# PWR_CORE.net
KiCad netlist of a schematic drawn in Altium Designer
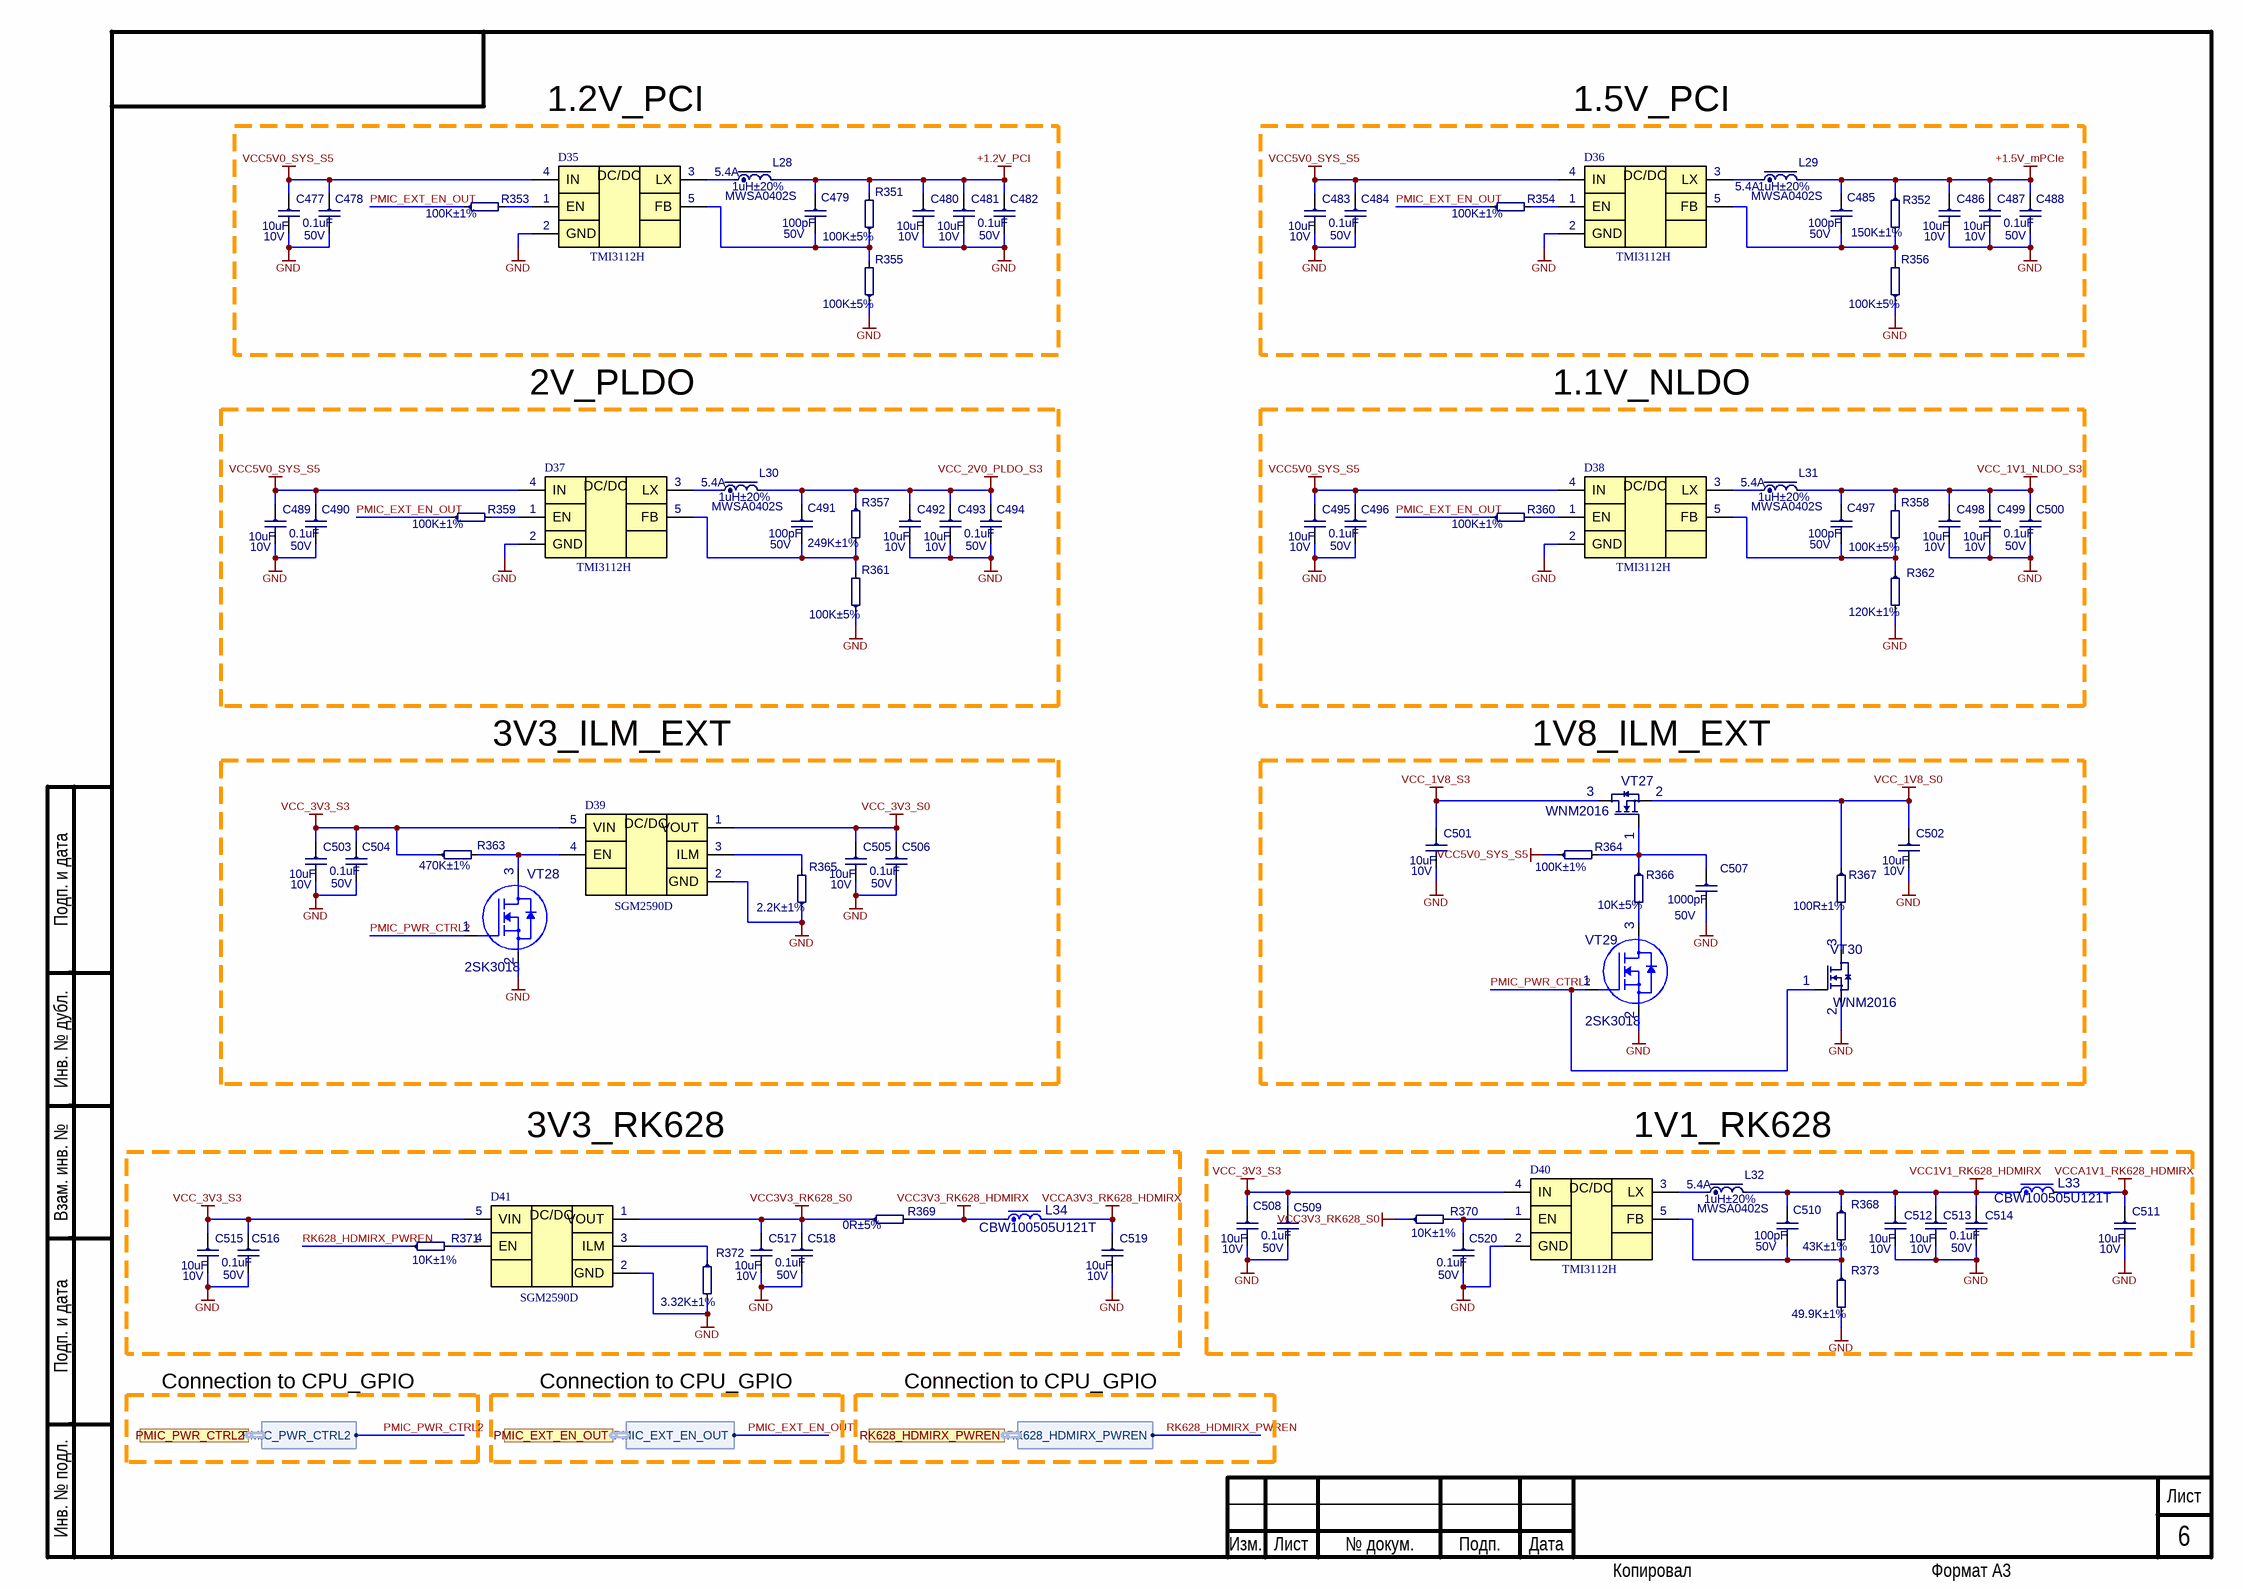
[diagram p0: PWR_CORE.SchDoc]

(export (version "E")
  (design (tool "Eeschema 10.0.6"))
  (components
    (comp (ref "C477")
      (value "10uF")
      (footprint "C0603")
      (fields
        (field (name "VOLTAGE") "10V")
        (field (name "PART NUMBER") "0603-X5R-10V-10uF±10%")
        (field (name "TOLERANCE") "10%")
        (field (name "MANUFACTURER") "Yageo")
      )
      (libsource (lib "ATB") (part "C"))
    )
    (comp (ref "C478")
      (value "0.1uF")
      (footprint "C0402")
      (fields
        (field (name "VOLTAGE") "50V")
        (field (name "PART NUMBER") "0402-X5R-50V-0.1uF±10%")
        (field (name "TOLERANCE") "10%")
        (field (name "MANUFACTURER") "Yageo")
      )
      (libsource (lib "ATB") (part "C"))
    )
    (comp (ref "C479")
      (value "100pF")
      (footprint "C0402")
      (fields
        (field (name "VOLTAGE") "50V")
        (field (name "PART NUMBER") "0402-NP0-50V-100pF±5%")
        (field (name "TOLERANCE") "5%")
        (field (name "MANUFACTURER") "Yageo")
      )
      (libsource (lib "ATB") (part "C"))
    )
    (comp (ref "C480")
      (value "10uF")
      (footprint "C0603")
      (fields
        (field (name "VOLTAGE") "10V")
        (field (name "PART NUMBER") "0603-X5R-10V-10uF±10%")
        (field (name "TOLERANCE") "10%")
        (field (name "MANUFACTURER") "Yageo")
      )
      (libsource (lib "ATB") (part "C"))
    )
    (comp (ref "C481")
      (value "10uF")
      (footprint "C0603")
      (fields
        (field (name "VOLTAGE") "10V")
        (field (name "PART NUMBER") "0603-X5R-10V-10uF±10%")
        (field (name "TOLERANCE") "10%")
        (field (name "MANUFACTURER") "Yageo")
      )
      (libsource (lib "ATB") (part "C"))
    )
    (comp (ref "C482")
      (value "0.1uF")
      (footprint "C0402")
      (fields
        (field (name "VOLTAGE") "50V")
        (field (name "PART NUMBER") "0402-X5R-50V-0.1uF±10%")
        (field (name "TOLERANCE") "10%")
        (field (name "MANUFACTURER") "Yageo")
      )
      (libsource (lib "ATB") (part "C"))
    )
    (comp (ref "C483")
      (value "10uF")
      (footprint "C0603")
      (fields
        (field (name "VOLTAGE") "10V")
        (field (name "PART NUMBER") "0603-X5R-10V-10uF±10%")
        (field (name "TOLERANCE") "10%")
        (field (name "MANUFACTURER") "Yageo")
      )
      (libsource (lib "ATB") (part "C"))
    )
    (comp (ref "C484")
      (value "0.1uF")
      (footprint "C0402")
      (fields
        (field (name "VOLTAGE") "50V")
        (field (name "PART NUMBER") "0402-X5R-50V-0.1uF±10%")
        (field (name "TOLERANCE") "10%")
        (field (name "MANUFACTURER") "Yageo")
      )
      (libsource (lib "ATB") (part "C"))
    )
    (comp (ref "C485")
      (value "100pF")
      (footprint "C0402")
      (fields
        (field (name "VOLTAGE") "50V")
        (field (name "PART NUMBER") "0402-NP0-50V-100pF±5%")
        (field (name "TOLERANCE") "5%")
        (field (name "MANUFACTURER") "Yageo")
      )
      (libsource (lib "ATB") (part "C"))
    )
    (comp (ref "C486")
      (value "10uF")
      (footprint "C0603")
      (fields
        (field (name "VOLTAGE") "10V")
        (field (name "PART NUMBER") "0603-X5R-10V-10uF±10%")
        (field (name "TOLERANCE") "10%")
        (field (name "MANUFACTURER") "Yageo")
      )
      (libsource (lib "ATB") (part "C"))
    )
    (comp (ref "C487")
      (value "10uF")
      (footprint "C0603")
      (fields
        (field (name "VOLTAGE") "10V")
        (field (name "PART NUMBER") "0603-X5R-10V-10uF±10%")
        (field (name "TOLERANCE") "10%")
        (field (name "MANUFACTURER") "Yageo")
      )
      (libsource (lib "ATB") (part "C"))
    )
    (comp (ref "C488")
      (value "0.1uF")
      (footprint "C0402")
      (fields
        (field (name "VOLTAGE") "50V")
        (field (name "PART NUMBER") "0402-X5R-50V-0.1uF±10%")
        (field (name "TOLERANCE") "10%")
        (field (name "MANUFACTURER") "Yageo")
      )
      (libsource (lib "ATB") (part "C"))
    )
    (comp (ref "C489")
      (value "10uF")
      (footprint "C0603")
      (fields
        (field (name "VOLTAGE") "10V")
        (field (name "PART NUMBER") "0603-X5R-10V-10uF±10%")
        (field (name "TOLERANCE") "10%")
        (field (name "MANUFACTURER") "Yageo")
      )
      (libsource (lib "ATB") (part "C"))
    )
    (comp (ref "C490")
      (value "0.1uF")
      (footprint "C0402")
      (fields
        (field (name "VOLTAGE") "50V")
        (field (name "PART NUMBER") "0402-X5R-50V-0.1uF±10%")
        (field (name "TOLERANCE") "10%")
        (field (name "MANUFACTURER") "Yageo")
      )
      (libsource (lib "ATB") (part "C"))
    )
    (comp (ref "C491")
      (value "100pF")
      (footprint "C0402")
      (fields
        (field (name "VOLTAGE") "50V")
        (field (name "PART NUMBER") "0402-NP0-50V-100pF±5%")
        (field (name "TOLERANCE") "5%")
        (field (name "MANUFACTURER") "Yageo")
      )
      (libsource (lib "ATB") (part "C"))
    )
    (comp (ref "C492")
      (value "10uF")
      (footprint "C0603")
      (fields
        (field (name "VOLTAGE") "10V")
        (field (name "PART NUMBER") "0603-X5R-10V-10uF±10%")
        (field (name "TOLERANCE") "10%")
        (field (name "MANUFACTURER") "Yageo")
      )
      (libsource (lib "ATB") (part "C"))
    )
    (comp (ref "C493")
      (value "10uF")
      (footprint "C0603")
      (fields
        (field (name "VOLTAGE") "10V")
        (field (name "PART NUMBER") "0603-X5R-10V-10uF±10%")
        (field (name "TOLERANCE") "10%")
        (field (name "MANUFACTURER") "Yageo")
      )
      (libsource (lib "ATB") (part "C"))
    )
    (comp (ref "C494")
      (value "0.1uF")
      (footprint "C0402")
      (fields
        (field (name "VOLTAGE") "50V")
        (field (name "PART NUMBER") "0402-X5R-50V-0.1uF±10%")
        (field (name "TOLERANCE") "10%")
        (field (name "MANUFACTURER") "Yageo")
      )
      (libsource (lib "ATB") (part "C"))
    )
    (comp (ref "C495")
      (value "10uF")
      (footprint "C0603")
      (fields
        (field (name "VOLTAGE") "10V")
        (field (name "PART NUMBER") "0603-X5R-10V-10uF±10%")
        (field (name "TOLERANCE") "10%")
        (field (name "MANUFACTURER") "Yageo")
      )
      (libsource (lib "ATB") (part "C"))
    )
    (comp (ref "C496")
      (value "0.1uF")
      (footprint "C0402")
      (fields
        (field (name "VOLTAGE") "50V")
        (field (name "PART NUMBER") "0402-X5R-50V-0.1uF±10%")
        (field (name "TOLERANCE") "10%")
        (field (name "MANUFACTURER") "Yageo")
      )
      (libsource (lib "ATB") (part "C"))
    )
    (comp (ref "C497")
      (value "100pF")
      (footprint "C0402")
      (fields
        (field (name "VOLTAGE") "50V")
        (field (name "PART NUMBER") "0402-NP0-50V-100pF±5%")
        (field (name "TOLERANCE") "5%")
        (field (name "MANUFACTURER") "Yageo")
      )
      (libsource (lib "ATB") (part "C"))
    )
    (comp (ref "C498")
      (value "10uF")
      (footprint "C0603")
      (fields
        (field (name "VOLTAGE") "10V")
        (field (name "PART NUMBER") "0603-X5R-10V-10uF±10%")
        (field (name "TOLERANCE") "10%")
        (field (name "MANUFACTURER") "Yageo")
      )
      (libsource (lib "ATB") (part "C"))
    )
    (comp (ref "C499")
      (value "10uF")
      (footprint "C0603")
      (fields
        (field (name "VOLTAGE") "10V")
        (field (name "PART NUMBER") "0603-X5R-10V-10uF±10%")
        (field (name "TOLERANCE") "10%")
        (field (name "MANUFACTURER") "Yageo")
      )
      (libsource (lib "ATB") (part "C"))
    )
    (comp (ref "C500")
      (value "0.1uF")
      (footprint "C0402")
      (fields
        (field (name "VOLTAGE") "50V")
        (field (name "PART NUMBER") "0402-X5R-50V-0.1uF±10%")
        (field (name "TOLERANCE") "10%")
        (field (name "MANUFACTURER") "Yageo")
      )
      (libsource (lib "ATB") (part "C"))
    )
    (comp (ref "C501")
      (value "10uF")
      (footprint "C0603")
      (fields
        (field (name "VOLTAGE") "10V")
        (field (name "PART NUMBER") "0603-X5R-10V-10uF±10%")
        (field (name "TOLERANCE") "10%")
        (field (name "MANUFACTURER") "Yageo")
      )
      (libsource (lib "ATB") (part "C"))
    )
    (comp (ref "C502")
      (value "10uF")
      (footprint "C0603")
      (fields
        (field (name "VOLTAGE") "10V")
        (field (name "PART NUMBER") "0603-X5R-10V-10uF±10%")
        (field (name "TOLERANCE") "10%")
        (field (name "MANUFACTURER") "Yageo")
      )
      (libsource (lib "ATB") (part "C"))
    )
    (comp (ref "C503")
      (value "10uF")
      (footprint "C0603")
      (fields
        (field (name "VOLTAGE") "10V")
        (field (name "PART NUMBER") "0603-X5R-10V-10uF±10%")
        (field (name "TOLERANCE") "10%")
        (field (name "MANUFACTURER") "Yageo")
      )
      (libsource (lib "ATB") (part "C"))
    )
    (comp (ref "C504")
      (value "0.1uF")
      (footprint "C0402")
      (fields
        (field (name "VOLTAGE") "50V")
        (field (name "PART NUMBER") "0402-X5R-50V-0.1uF±10%")
        (field (name "TOLERANCE") "10%")
        (field (name "MANUFACTURER") "Yageo")
      )
      (libsource (lib "ATB") (part "C"))
    )
    (comp (ref "C505")
      (value "10uF")
      (footprint "C0603")
      (fields
        (field (name "VOLTAGE") "10V")
        (field (name "PART NUMBER") "0603-X5R-10V-10uF±10%")
        (field (name "TOLERANCE") "10%")
        (field (name "MANUFACTURER") "Yageo")
      )
      (libsource (lib "ATB") (part "C"))
    )
    (comp (ref "C506")
      (value "0.1uF")
      (footprint "C0402")
      (fields
        (field (name "VOLTAGE") "50V")
        (field (name "PART NUMBER") "0402-X5R-50V-0.1uF±10%")
        (field (name "TOLERANCE") "10%")
        (field (name "MANUFACTURER") "Yageo")
      )
      (libsource (lib "ATB") (part "C"))
    )
    (comp (ref "C507")
      (value "1000pF")
      (footprint "C0402")
      (fields
        (field (name "VOLTAGE") "50V")
        (field (name "PART NUMBER") "0402-NP0-50V-1000pF±5%")
        (field (name "TOLERANCE") "5%")
        (field (name "MANUFACTURER") "Yageo")
      )
      (libsource (lib "ATB") (part "C"))
    )
    (comp (ref "C508")
      (value "10uF")
      (footprint "C0603")
      (fields
        (field (name "VOLTAGE") "10V")
        (field (name "PART NUMBER") "0603-X5R-10V-10uF±10%")
        (field (name "TOLERANCE") "10%")
        (field (name "MANUFACTURER") "Yageo")
      )
      (libsource (lib "ATB") (part "C"))
    )
    (comp (ref "C509")
      (value "0.1uF")
      (footprint "C0402")
      (fields
        (field (name "VOLTAGE") "50V")
        (field (name "PART NUMBER") "0402-X5R-50V-0.1uF±10%")
        (field (name "TOLERANCE") "10%")
        (field (name "MANUFACTURER") "Yageo")
      )
      (libsource (lib "ATB") (part "C"))
    )
    (comp (ref "C510")
      (value "100pF")
      (footprint "C0402")
      (fields
        (field (name "VOLTAGE") "50V")
        (field (name "PART NUMBER") "0402-NP0-50V-100pF±5%")
        (field (name "TOLERANCE") "5%")
        (field (name "MANUFACTURER") "Yageo")
      )
      (libsource (lib "ATB") (part "C"))
    )
    (comp (ref "C511")
      (value "10uF")
      (footprint "C0603")
      (fields
        (field (name "VOLTAGE") "10V")
        (field (name "PART NUMBER") "0603-X5R-10V-10uF±10%")
        (field (name "TOLERANCE") "10%")
        (field (name "MANUFACTURER") "Yageo")
      )
      (libsource (lib "ATB") (part "C"))
    )
    (comp (ref "C512")
      (value "10uF")
      (footprint "C0603")
      (fields
        (field (name "VOLTAGE") "10V")
        (field (name "PART NUMBER") "0603-X5R-10V-10uF±10%")
        (field (name "TOLERANCE") "10%")
        (field (name "MANUFACTURER") "Yageo")
      )
      (libsource (lib "ATB") (part "C"))
    )
    (comp (ref "C513")
      (value "10uF")
      (footprint "C0603")
      (fields
        (field (name "VOLTAGE") "10V")
        (field (name "PART NUMBER") "0603-X5R-10V-10uF±10%")
        (field (name "TOLERANCE") "10%")
        (field (name "MANUFACTURER") "Yageo")
      )
      (libsource (lib "ATB") (part "C"))
    )
    (comp (ref "C514")
      (value "0.1uF")
      (footprint "C0402")
      (fields
        (field (name "VOLTAGE") "50V")
        (field (name "PART NUMBER") "0402-X5R-50V-0.1uF±10%")
        (field (name "TOLERANCE") "10%")
        (field (name "MANUFACTURER") "Yageo")
      )
      (libsource (lib "ATB") (part "C"))
    )
    (comp (ref "C515")
      (value "10uF")
      (footprint "C0603")
      (fields
        (field (name "VOLTAGE") "10V")
        (field (name "PART NUMBER") "0603-X5R-10V-10uF±10%")
        (field (name "TOLERANCE") "10%")
        (field (name "MANUFACTURER") "Yageo")
      )
      (libsource (lib "ATB") (part "C"))
    )
    (comp (ref "C516")
      (value "0.1uF")
      (footprint "C0402")
      (fields
        (field (name "VOLTAGE") "50V")
        (field (name "PART NUMBER") "0402-X5R-50V-0.1uF±10%")
        (field (name "TOLERANCE") "10%")
        (field (name "MANUFACTURER") "Yageo")
      )
      (libsource (lib "ATB") (part "C"))
    )
    (comp (ref "C517")
      (value "10uF")
      (footprint "C0603")
      (fields
        (field (name "VOLTAGE") "10V")
        (field (name "PART NUMBER") "0603-X5R-10V-10uF±10%")
        (field (name "TOLERANCE") "10%")
        (field (name "MANUFACTURER") "Yageo")
      )
      (libsource (lib "ATB") (part "C"))
    )
    (comp (ref "C518")
      (value "0.1uF")
      (footprint "C0402")
      (fields
        (field (name "VOLTAGE") "50V")
        (field (name "PART NUMBER") "0402-X5R-50V-0.1uF±10%")
        (field (name "TOLERANCE") "10%")
        (field (name "MANUFACTURER") "Yageo")
      )
      (libsource (lib "ATB") (part "C"))
    )
    (comp (ref "C519")
      (value "10uF")
      (footprint "C0603")
      (fields
        (field (name "VOLTAGE") "10V")
        (field (name "PART NUMBER") "0603-X5R-10V-10uF±10%")
        (field (name "TOLERANCE") "10%")
        (field (name "MANUFACTURER") "Yageo")
      )
      (libsource (lib "ATB") (part "C"))
    )
    (comp (ref "C520")
      (value "0.1uF")
      (footprint "C0402")
      (fields
        (field (name "VOLTAGE") "50V")
        (field (name "PART NUMBER") "0402-X5R-50V-0.1uF±10%")
        (field (name "TOLERANCE") "10%")
        (field (name "MANUFACTURER") "Yageo")
      )
      (libsource (lib "ATB") (part "C"))
    )
    (comp (ref "D35")
      (value "TMI3112H")
      (footprint "TMI3112H")
      (description "Buck 2.3MHz Adjustable 2A 600mV~5.5V SOT-23-5 Voltage Regulators - DC DC Switching Regulators RoHS")
      (fields (field (name "MANUFACTURER") "TMI"))
      (libsource (lib "LIB_RK") (part "TMI3112H"))
    )
    (comp (ref "D36")
      (value "TMI3112H")
      (footprint "TMI3112H")
      (description "Buck 2.3MHz Adjustable 2A 600mV~5.5V SOT-23-5 Voltage Regulators - DC DC Switching Regulators RoHS")
      (fields (field (name "MANUFACTURER") "TMI"))
      (libsource (lib "LIB_RK") (part "TMI3112H"))
    )
    (comp (ref "D37")
      (value "TMI3112H")
      (footprint "TMI3112H")
      (description "Buck 2.3MHz Adjustable 2A 600mV~5.5V SOT-23-5 Voltage Regulators - DC DC Switching Regulators RoHS")
      (fields (field (name "MANUFACTURER") "TMI"))
      (libsource (lib "LIB_RK") (part "TMI3112H"))
    )
    (comp (ref "D38")
      (value "TMI3112H")
      (footprint "TMI3112H")
      (description "Buck 2.3MHz Adjustable 2A 600mV~5.5V SOT-23-5 Voltage Regulators - DC DC Switching Regulators RoHS")
      (fields (field (name "MANUFACTURER") "TMI"))
      (libsource (lib "LIB_RK") (part "TMI3112H"))
    )
    (comp (ref "D39")
      (value "SGM2590D")
      (footprint "SGM2590D")
      (fields (field (name "MANUFACTURER") "SGM"))
      (libsource (lib "LIB_RK") (part "SGM2590D"))
    )
    (comp (ref "D40")
      (value "TMI3112H")
      (footprint "TMI3112H")
      (description "Buck 2.3MHz Adjustable 2A 600mV~5.5V SOT-23-5 Voltage Regulators - DC DC Switching Regulators RoHS")
      (fields (field (name "MANUFACTURER") "TMI"))
      (libsource (lib "LIB_RK") (part "TMI3112H"))
    )
    (comp (ref "D41")
      (value "SGM2590D")
      (footprint "SGM2590D")
      (fields (field (name "MANUFACTURER") "SGM"))
      (libsource (lib "LIB_RK") (part "SGM2590D"))
    )
    (comp (ref "L28")
      (value "1uH±20%")
      (footprint "MWSA0402S")
      (description "5.4A 1uH ±20% 5.6A SMD 4.4x4.2mm Power Inductor")
      (fields
        (field (name "CURRENT") "5.4A")
        (field (name "CASE") "MWSA0402S")
        (field (name "PART NUMBER") "MWSA0402S-1R0MT")
        (field (name "TOLERANCE") "20%")
      )
      (libsource (lib "") (part "L_1"))
    )
    (comp (ref "L29")
      (value "1uH±20%")
      (footprint "MWSA0402S")
      (description "5.4A 1uH ±20% 5.6A SMD 4.4x4.2mm Power Inductor")
      (fields
        (field (name "CURRENT") "5.4A")
        (field (name "CASE") "MWSA0402S")
        (field (name "PART NUMBER") "MWSA0402S-1R0MT")
        (field (name "TOLERANCE") "20%")
      )
      (libsource (lib "") (part "L_1"))
    )
    (comp (ref "L30")
      (value "1uH±20%")
      (footprint "MWSA0402S")
      (description "5.4A 1uH ±20% 5.6A SMD 4.4x4.2mm Power Inductor")
      (fields
        (field (name "CURRENT") "5.4A")
        (field (name "CASE") "MWSA0402S")
        (field (name "PART NUMBER") "MWSA0402S-1R0MT")
        (field (name "TOLERANCE") "20%")
      )
      (libsource (lib "") (part "L_1"))
    )
    (comp (ref "L31")
      (value "1uH±20%")
      (footprint "MWSA0402S")
      (description "5.4A 1uH ±20% 5.6A SMD 4.4x4.2mm Power Inductor")
      (fields
        (field (name "CURRENT") "5.4A")
        (field (name "CASE") "MWSA0402S")
        (field (name "PART NUMBER") "MWSA0402S-1R0MT")
        (field (name "TOLERANCE") "20%")
      )
      (libsource (lib "") (part "L_1"))
    )
    (comp (ref "L32")
      (value "1uH±20%")
      (footprint "MWSA0402S")
      (description "5.4A 1uH ±20% 5.6A SMD 4.4x4.2mm Power Inductor")
      (fields
        (field (name "CURRENT") "5.4A")
        (field (name "CASE") "MWSA0402S")
        (field (name "PART NUMBER") "MWSA0402S-1R0MT")
        (field (name "TOLERANCE") "20%")
      )
      (libsource (lib "") (part "L_1"))
    )
    (comp (ref "L33")
      (value "CBW100505U121T")
      (footprint "L0402")
      (description "120Ω@100MHz  Ferrite Beads")
      (fields (field (name "TOLERANCE") "25%") (field (name "MANUFACTURER") "Murata Electronics"))
      (libsource (lib "ATB") (part "L"))
    )
    (comp (ref "L34")
      (value "CBW100505U121T")
      (footprint "L0402")
      (description "120Ω@100MHz  Ferrite Beads")
      (fields (field (name "TOLERANCE") "25%") (field (name "MANUFACTURER") "Murata Electronics"))
      (libsource (lib "ATB") (part "L"))
    )
    (comp (ref "R351")
      (value "100K±5%")
      (footprint "R0402")
      (fields
        (field (name "PART NUMBER") "0402-0.0625W-100K-100ppm±5%")
        (field (name "TOLERANCE") "5%")
        (field (name "MANUFACTURER") "Yageo")
      )
      (libsource (lib "ATB") (part "R"))
    )
    (comp (ref "R352")
      (value "150K±1%")
      (footprint "R0402")
      (fields
        (field (name "PART NUMBER") "0402-0.0625W-150K-100ppm±1%")
        (field (name "TOLERANCE") "1%")
        (field (name "MANUFACTURER") "Yageo")
      )
      (libsource (lib "ATB") (part "R"))
    )
    (comp (ref "R353")
      (value "100K±1%")
      (footprint "R0402")
      (description "Chip Resistor 0402 100kΩ ±1% 50V ±100ppm/℃ Thick Film")
      (fields (field (name "PART NUMBER") "0402-0.0625W-100K-100ppm±1%") (field (name "TOLERANCE") "1%"))
      (libsource (lib "ATB") (part "R"))
    )
    (comp (ref "R354")
      (value "100K±1%")
      (footprint "R0402")
      (description "Chip Resistor 0402 100kΩ ±1% 50V ±100ppm/℃ Thick Film")
      (fields (field (name "PART NUMBER") "0402-0.0625W-100K-100ppm±1%") (field (name "TOLERANCE") "1%"))
      (libsource (lib "ATB") (part "R"))
    )
    (comp (ref "R355")
      (value "100K±5%")
      (footprint "R0402")
      (fields
        (field (name "PART NUMBER") "0402-0.0625W-100K-100ppm±5%")
        (field (name "TOLERANCE") "5%")
        (field (name "MANUFACTURER") "Yageo")
      )
      (libsource (lib "ATB") (part "R"))
    )
    (comp (ref "R356")
      (value "100K±5%")
      (footprint "R0402")
      (fields
        (field (name "PART NUMBER") "0402-0.0625W-100K-100ppm±5%")
        (field (name "TOLERANCE") "5%")
        (field (name "MANUFACTURER") "Yageo")
      )
      (libsource (lib "ATB") (part "R"))
    )
    (comp (ref "R357")
      (value "249K±1%")
      (footprint "R0402")
      (fields
        (field (name "PART NUMBER") "0402-0.0625W-249K-100ppm±1%")
        (field (name "TOLERANCE") "1%")
        (field (name "MANUFACTURER") "Yageo")
      )
      (libsource (lib "ATB") (part "R"))
    )
    (comp (ref "R358")
      (value "100K±5%")
      (footprint "R0402")
      (fields
        (field (name "PART NUMBER") "0402-0.0625W-100K-100ppm±5%")
        (field (name "TOLERANCE") "5%")
        (field (name "MANUFACTURER") "Yageo")
      )
      (libsource (lib "ATB") (part "R"))
    )
    (comp (ref "R359")
      (value "100K±1%")
      (footprint "R0402")
      (description "Chip Resistor 0402 100kΩ ±1% 50V ±100ppm/℃ Thick Film")
      (fields (field (name "PART NUMBER") "0402-0.0625W-100K-100ppm±1%") (field (name "TOLERANCE") "1%"))
      (libsource (lib "ATB") (part "R"))
    )
    (comp (ref "R360")
      (value "100K±1%")
      (footprint "R0402")
      (description "Chip Resistor 0402 100kΩ ±1% 50V ±100ppm/℃ Thick Film")
      (fields (field (name "PART NUMBER") "0402-0.0625W-100K-100ppm±1%") (field (name "TOLERANCE") "1%"))
      (libsource (lib "ATB") (part "R"))
    )
    (comp (ref "R361")
      (value "100K±5%")
      (footprint "R0402")
      (fields
        (field (name "PART NUMBER") "0402-0.0625W-100K-100ppm±5%")
        (field (name "TOLERANCE") "5%")
        (field (name "MANUFACTURER") "Yageo")
      )
      (libsource (lib "ATB") (part "R"))
    )
    (comp (ref "R362")
      (value "120K±1%")
      (footprint "R0402")
      (fields
        (field (name "PART NUMBER") "0402-0.0625W-120K-100ppm±1%")
        (field (name "TOLERANCE") "1%")
        (field (name "MANUFACTURER") "Yageo")
      )
      (libsource (lib "ATB") (part "R"))
    )
    (comp (ref "R363")
      (value "470K±1%")
      (footprint "R0402")
      (fields
        (field (name "PART NUMBER") "0402-0.0625W-470K-100ppm±1%")
        (field (name "TOLERANCE") "1%")
        (field (name "MANUFACTURER") "Yageo")
      )
      (libsource (lib "ATB") (part "R"))
    )
    (comp (ref "R364")
      (value "100K±1%")
      (footprint "R0402")
      (description "Chip Resistor 0402 100kΩ ±1% 50V ±100ppm/℃ Thick Film")
      (fields (field (name "PART NUMBER") "0402-0.0625W-100K-100ppm±1%") (field (name "TOLERANCE") "1%"))
      (libsource (lib "ATB") (part "R"))
    )
    (comp (ref "R365")
      (value "2.2K±1%")
      (footprint "R0402")
      (fields
        (field (name "PART NUMBER") "0402-0.0625W-2.2K-100ppm±1%")
        (field (name "TOLERANCE") "1%")
        (field (name "MANUFACTURER") "Yageo")
      )
      (libsource (lib "ATB") (part "R"))
    )
    (comp (ref "R366")
      (value "10K±5%")
      (footprint "R0402")
      (fields
        (field (name "PART NUMBER") "0402-0.0625W-10K-100ppm±5%")
        (field (name "TOLERANCE") "5%")
        (field (name "MANUFACTURER") "Yageo")
      )
      (libsource (lib "ATB") (part "R"))
    )
    (comp (ref "R367")
      (value "100R±1%")
      (footprint "R0402")
      (description "Chip Resistor 0402 100Ω ±1% 50V ±100ppm/℃ Thick Film")
      (fields (field (name "PART NUMBER") "0402-0.0625W-100R-100ppm±1%") (field (name "TOLERANCE") "1%"))
      (libsource (lib "ATB") (part "R"))
    )
    (comp (ref "R368")
      (value "43K±1%")
      (footprint "R0402")
      (fields
        (field (name "PART NUMBER") "0402-0.0625W-43K-100ppm±1%")
        (field (name "TOLERANCE") "1%")
        (field (name "MANUFACTURER") "Yageo")
      )
      (libsource (lib "ATB") (part "R"))
    )
    (comp (ref "R369")
      (value "0R±5%")
      (footprint "R0603")
      (description "Chip Resistor 0603 0Ω ±5% 50V ±100ppm/℃ Thick Film")
      (fields (field (name "PART NUMBER") "0603-0.1W-0R-100ppm±5%") (field (name "TOLERANCE") "5%"))
      (libsource (lib "ATB") (part "R"))
    )
    (comp (ref "R370")
      (value "10K±1%")
      (footprint "R0402")
      (description "Chip Resistor 0402 10kΩ ±1% 50V ±100ppm/℃ Thick Film")
      (fields (field (name "PART NUMBER") "0402-0.0625W-10K-100ppm±1%") (field (name "TOLERANCE") "1%"))
      (libsource (lib "ATB") (part "R"))
    )
    (comp (ref "R371")
      (value "10K±1%")
      (footprint "R0402")
      (description "Chip Resistor 0402 10kΩ ±1% 50V ±100ppm/℃ Thick Film")
      (fields (field (name "PART NUMBER") "0402-0.0625W-10K-100ppm±1%") (field (name "TOLERANCE") "1%"))
      (libsource (lib "ATB") (part "R"))
    )
    (comp (ref "R372")
      (value "3.32K±1%")
      (footprint "R0603")
      (fields
        (field (name "PART NUMBER") "0603-0.1W-3.32K-100ppm±1%")
        (field (name "TOLERANCE") "1%")
        (field (name "MANUFACTURER") "Viking Tech Corp.(VIKING)")
      )
      (libsource (lib "ATB") (part "R"))
    )
    (comp (ref "R373")
      (value "49.9K±1%")
      (footprint "R0402")
      (description "Chip Resistor 0402 49.9kΩ ±1% 50V ±100ppm/℃ Thick Film")
      (fields (field (name "PART NUMBER") "0402-0.0625W-49.9K-100ppm±1%") (field (name "TOLERANCE") "1%"))
      (libsource (lib "ATB") (part "R"))
    )
    (comp (ref "VT27")
      (value "WNM2016")
      (footprint "SOT23")
      (description "60V 3A 0.35W Surface Mount SOT-23")
      (fields (field (name "VOLTAGE") "60V") (field (name "MANUFACTURER") "KUU Semiconductor"))
      (libsource (lib "ATB") (part "BSS138"))
    )
    (comp (ref "VT28")
      (value "2SK3018")
      (footprint "2SK3018")
      (description "N-Channel")
      (libsource (lib "LIB_RK") (part "2SK3018"))
    )
    (comp (ref "VT29")
      (value "2SK3018")
      (footprint "2SK3018")
      (description "N-Channel")
      (libsource (lib "LIB_RK") (part "2SK3018"))
    )
    (comp (ref "VT30")
      (value "WNM2016")
      (footprint "SOT23")
      (description "60V 3A 0.35W Surface Mount SOT-23")
      (fields (field (name "VOLTAGE") "60V") (field (name "MANUFACTURER") "KUU Semiconductor"))
      (libsource (lib "ATB") (part "BSS138"))
    )
  )
  (nets
    (net (code "1") (name "+1.2V_PCI") (class "Default")
      (node (ref "C479") (pin "1") (pinfunction "1_1") (pintype "passive"))
      (node (ref "C480") (pin "1") (pinfunction "1_1") (pintype "passive"))
      (node (ref "C481") (pin "1") (pinfunction "1_1") (pintype "passive"))
      (node (ref "C482") (pin "1") (pinfunction "1_1") (pintype "passive"))
      (node (ref "L28") (pin "2") (pinfunction "2_2") (pintype "passive"))
      (node (ref "R351") (pin "2") (pinfunction "2_2") (pintype "passive"))
    )
    (net (code "2") (name "+1.5V_mPCIe") (class "Default")
      (node (ref "C485") (pin "1") (pinfunction "1_1") (pintype "passive"))
      (node (ref "C486") (pin "1") (pinfunction "1_1") (pintype "passive"))
      (node (ref "C487") (pin "1") (pinfunction "1_1") (pintype "passive"))
      (node (ref "C488") (pin "1") (pinfunction "1_1") (pintype "passive"))
      (node (ref "L29") (pin "2") (pinfunction "2_2") (pintype "passive"))
      (node (ref "R352") (pin "1") (pinfunction "1_1") (pintype "passive"))
    )
    (net (code "3") (name "/PMIC_EXT_EN_OUT") (class "Default")
      (node (ref "R353") (pin "1") (pinfunction "1_1") (pintype "passive"))
      (node (ref "R354") (pin "1") (pinfunction "1_1") (pintype "passive"))
      (node (ref "R359") (pin "1") (pinfunction "1_1") (pintype "passive"))
      (node (ref "R360") (pin "1") (pinfunction "1_1") (pintype "passive"))
    )
    (net (code "4") (name "/PMIC_PWR_CTRL2") (class "Default")
      (node (ref "VT28") (pin "1") (pinfunction "G_1") (pintype "passive"))
      (node (ref "VT29") (pin "1") (pinfunction "G_1") (pintype "passive"))
      (node (ref "VT30") (pin "1") (pinfunction "G_1") (pintype "passive"))
    )
    (net (code "5") (name "/RK628_HDMIRX_PWREN") (class "Default")
      (node (ref "R371") (pin "1") (pinfunction "1_1") (pintype "passive"))
    )
    (net (code "9") (name "GND") (class "Default")
      (node (ref "C477") (pin "2") (pinfunction "2_2") (pintype "passive"))
      (node (ref "C478") (pin "2") (pinfunction "2_2") (pintype "passive"))
      (node (ref "C480") (pin "2") (pinfunction "2_2") (pintype "passive"))
      (node (ref "C481") (pin "2") (pinfunction "2_2") (pintype "passive"))
      (node (ref "C482") (pin "2") (pinfunction "2_2") (pintype "passive"))
      (node (ref "C483") (pin "2") (pinfunction "2_2") (pintype "passive"))
      (node (ref "C484") (pin "2") (pinfunction "2_2") (pintype "passive"))
      (node (ref "C486") (pin "2") (pinfunction "2_2") (pintype "passive"))
      (node (ref "C487") (pin "2") (pinfunction "2_2") (pintype "passive"))
      (node (ref "C488") (pin "2") (pinfunction "2_2") (pintype "passive"))
      (node (ref "C489") (pin "2") (pinfunction "2_2") (pintype "passive"))
      (node (ref "C490") (pin "2") (pinfunction "2_2") (pintype "passive"))
      (node (ref "C492") (pin "2") (pinfunction "2_2") (pintype "passive"))
      (node (ref "C493") (pin "2") (pinfunction "2_2") (pintype "passive"))
      (node (ref "C494") (pin "2") (pinfunction "2_2") (pintype "passive"))
      (node (ref "C495") (pin "2") (pinfunction "2_2") (pintype "passive"))
      (node (ref "C496") (pin "2") (pinfunction "2_2") (pintype "passive"))
      (node (ref "C498") (pin "2") (pinfunction "2_2") (pintype "passive"))
      (node (ref "C499") (pin "2") (pinfunction "2_2") (pintype "passive"))
      (node (ref "C500") (pin "2") (pinfunction "2_2") (pintype "passive"))
      (node (ref "C501") (pin "2") (pinfunction "2_2") (pintype "passive"))
      (node (ref "C502") (pin "2") (pinfunction "2_2") (pintype "passive"))
      (node (ref "C503") (pin "2") (pinfunction "2_2") (pintype "passive"))
      (node (ref "C504") (pin "2") (pinfunction "2_2") (pintype "passive"))
      (node (ref "C505") (pin "2") (pinfunction "2_2") (pintype "passive"))
      (node (ref "C506") (pin "2") (pinfunction "2_2") (pintype "passive"))
      (node (ref "C507") (pin "2") (pinfunction "2_2") (pintype "passive"))
      (node (ref "C508") (pin "2") (pinfunction "2_2") (pintype "passive"))
      (node (ref "C509") (pin "2") (pinfunction "2_2") (pintype "passive"))
      (node (ref "C511") (pin "2") (pinfunction "2_2") (pintype "passive"))
      (node (ref "C512") (pin "2") (pinfunction "2_2") (pintype "passive"))
      (node (ref "C513") (pin "2") (pinfunction "2_2") (pintype "passive"))
      (node (ref "C514") (pin "2") (pinfunction "2_2") (pintype "passive"))
      (node (ref "C515") (pin "2") (pinfunction "2_2") (pintype "passive"))
      (node (ref "C516") (pin "2") (pinfunction "2_2") (pintype "passive"))
      (node (ref "C517") (pin "2") (pinfunction "2_2") (pintype "passive"))
      (node (ref "C518") (pin "2") (pinfunction "2_2") (pintype "passive"))
      (node (ref "C519") (pin "2") (pinfunction "2_2") (pintype "passive"))
      (node (ref "C520") (pin "2") (pinfunction "2_2") (pintype "passive"))
      (node (ref "D35") (pin "2") (pinfunction "GND_2") (pintype "passive"))
      (node (ref "D36") (pin "2") (pinfunction "GND_2") (pintype "passive"))
      (node (ref "D37") (pin "2") (pinfunction "GND_2") (pintype "passive"))
      (node (ref "D38") (pin "2") (pinfunction "GND_2") (pintype "passive"))
      (node (ref "D39") (pin "2") (pinfunction "GND_2") (pintype "passive"))
      (node (ref "D40") (pin "2") (pinfunction "GND_2") (pintype "passive"))
      (node (ref "D41") (pin "2") (pinfunction "GND_2") (pintype "passive"))
      (node (ref "R355") (pin "1") (pinfunction "1_1") (pintype "passive"))
      (node (ref "R356") (pin "1") (pinfunction "1_1") (pintype "passive"))
      (node (ref "R361") (pin "1") (pinfunction "1_1") (pintype "passive"))
      (node (ref "R362") (pin "2") (pinfunction "2_2") (pintype "passive"))
      (node (ref "R365") (pin "1") (pinfunction "1_1") (pintype "passive"))
      (node (ref "R372") (pin "2") (pinfunction "2_2") (pintype "passive"))
      (node (ref "R373") (pin "2") (pinfunction "2_2") (pintype "passive"))
      (node (ref "VT28") (pin "2") (pinfunction "S_2") (pintype "passive"))
      (node (ref "VT29") (pin "2") (pinfunction "S_2") (pintype "passive"))
      (node (ref "VT30") (pin "2") (pinfunction "S_2") (pintype "passive"))
    )
    (net (code "10") (name "Net-(D35-EN)") (class "Default")
      (node (ref "D35") (pin "1") (pinfunction "EN_1") (pintype "passive"))
      (node (ref "R353") (pin "2") (pinfunction "2_2") (pintype "passive"))
    )
    (net (code "11") (name "Net-(D35-FB)") (class "Default")
      (node (ref "C479") (pin "2") (pinfunction "2_2") (pintype "passive"))
      (node (ref "D35") (pin "5") (pinfunction "FB_5") (pintype "passive"))
      (node (ref "R351") (pin "1") (pinfunction "1_1") (pintype "passive"))
      (node (ref "R355") (pin "2") (pinfunction "2_2") (pintype "passive"))
    )
    (net (code "12") (name "Net-(D35-LX)") (class "Default")
      (node (ref "D35") (pin "3") (pinfunction "LX_3") (pintype "passive"))
      (node (ref "L28") (pin "1") (pinfunction "1_1") (pintype "passive"))
    )
    (net (code "13") (name "Net-(D36-EN)") (class "Default")
      (node (ref "D36") (pin "1") (pinfunction "EN_1") (pintype "passive"))
      (node (ref "R354") (pin "2") (pinfunction "2_2") (pintype "passive"))
    )
    (net (code "14") (name "Net-(D36-FB)") (class "Default")
      (node (ref "C485") (pin "2") (pinfunction "2_2") (pintype "passive"))
      (node (ref "D36") (pin "5") (pinfunction "FB_5") (pintype "passive"))
      (node (ref "R352") (pin "2") (pinfunction "2_2") (pintype "passive"))
      (node (ref "R356") (pin "2") (pinfunction "2_2") (pintype "passive"))
    )
    (net (code "15") (name "Net-(D36-LX)") (class "Default")
      (node (ref "D36") (pin "3") (pinfunction "LX_3") (pintype "passive"))
      (node (ref "L29") (pin "1") (pinfunction "1_1") (pintype "passive"))
    )
    (net (code "16") (name "Net-(D37-EN)") (class "Default")
      (node (ref "D37") (pin "1") (pinfunction "EN_1") (pintype "passive"))
      (node (ref "R359") (pin "2") (pinfunction "2_2") (pintype "passive"))
    )
    (net (code "17") (name "Net-(D37-FB)") (class "Default")
      (node (ref "C491") (pin "2") (pinfunction "2_2") (pintype "passive"))
      (node (ref "D37") (pin "5") (pinfunction "FB_5") (pintype "passive"))
      (node (ref "R357") (pin "2") (pinfunction "2_2") (pintype "passive"))
      (node (ref "R361") (pin "2") (pinfunction "2_2") (pintype "passive"))
    )
    (net (code "18") (name "Net-(D37-LX)") (class "Default")
      (node (ref "D37") (pin "3") (pinfunction "LX_3") (pintype "passive"))
      (node (ref "L30") (pin "1") (pinfunction "1_1") (pintype "passive"))
    )
    (net (code "19") (name "Net-(D38-EN)") (class "Default")
      (node (ref "D38") (pin "1") (pinfunction "EN_1") (pintype "passive"))
      (node (ref "R360") (pin "2") (pinfunction "2_2") (pintype "passive"))
    )
    (net (code "20") (name "Net-(D38-FB)") (class "Default")
      (node (ref "C497") (pin "2") (pinfunction "2_2") (pintype "passive"))
      (node (ref "D38") (pin "5") (pinfunction "FB_5") (pintype "passive"))
      (node (ref "R358") (pin "1") (pinfunction "1_1") (pintype "passive"))
      (node (ref "R362") (pin "1") (pinfunction "1_1") (pintype "passive"))
    )
    (net (code "21") (name "Net-(D38-LX)") (class "Default")
      (node (ref "D38") (pin "3") (pinfunction "LX_3") (pintype "passive"))
      (node (ref "L31") (pin "1") (pinfunction "1_1") (pintype "passive"))
    )
    (net (code "22") (name "Net-(D39-EN)") (class "Default")
      (node (ref "D39") (pin "4") (pinfunction "EN_4") (pintype "passive"))
      (node (ref "R363") (pin "2") (pinfunction "2_2") (pintype "passive"))
      (node (ref "VT28") (pin "3") (pinfunction "D_3") (pintype "passive"))
    )
    (net (code "23") (name "Net-(D39-ILM)") (class "Default")
      (node (ref "D39") (pin "3") (pinfunction "ILM_3") (pintype "passive"))
      (node (ref "R365") (pin "2") (pinfunction "2_2") (pintype "passive"))
    )
    (net (code "24") (name "Net-(D40-EN)") (class "Default")
      (node (ref "C520") (pin "1") (pinfunction "1_1") (pintype "passive"))
      (node (ref "D40") (pin "1") (pinfunction "EN_1") (pintype "passive"))
      (node (ref "R370") (pin "2") (pinfunction "2_2") (pintype "passive"))
    )
    (net (code "25") (name "Net-(D40-FB)") (class "Default")
      (node (ref "C510") (pin "2") (pinfunction "2_2") (pintype "passive"))
      (node (ref "D40") (pin "5") (pinfunction "FB_5") (pintype "passive"))
      (node (ref "R368") (pin "2") (pinfunction "2_2") (pintype "passive"))
      (node (ref "R373") (pin "1") (pinfunction "1_1") (pintype "passive"))
    )
    (net (code "26") (name "Net-(D40-LX)") (class "Default")
      (node (ref "D40") (pin "3") (pinfunction "LX_3") (pintype "passive"))
      (node (ref "L32") (pin "1") (pinfunction "1_1") (pintype "passive"))
    )
    (net (code "27") (name "Net-(D41-EN)") (class "Default")
      (node (ref "D41") (pin "4") (pinfunction "EN_4") (pintype "passive"))
      (node (ref "R371") (pin "2") (pinfunction "2_2") (pintype "passive"))
    )
    (net (code "28") (name "Net-(D41-ILM)") (class "Default")
      (node (ref "D41") (pin "3") (pinfunction "ILM_3") (pintype "passive"))
      (node (ref "R372") (pin "1") (pinfunction "1_1") (pintype "passive"))
    )
    (net (code "29") (name "Net-(VT27-G)") (class "Default")
      (node (ref "C507") (pin "1") (pinfunction "1_1") (pintype "passive"))
      (node (ref "R364") (pin "2") (pinfunction "2_2") (pintype "passive"))
      (node (ref "R366") (pin "1") (pinfunction "1_1") (pintype "passive"))
      (node (ref "VT27") (pin "1") (pinfunction "G_1") (pintype "passive"))
    )
    (net (code "30") (name "Net-(VT29-D)") (class "Default")
      (node (ref "R366") (pin "2") (pinfunction "2_2") (pintype "passive"))
      (node (ref "VT29") (pin "3") (pinfunction "D_3") (pintype "passive"))
    )
    (net (code "31") (name "Net-(VT30-D)") (class "Default")
      (node (ref "R367") (pin "2") (pinfunction "2_2") (pintype "passive"))
      (node (ref "VT30") (pin "3") (pinfunction "D_3") (pintype "passive"))
    )
    (net (code "32") (name "VCC1V1_RK628_HDMIRX") (class "Default")
      (node (ref "C510") (pin "1") (pinfunction "1_1") (pintype "passive"))
      (node (ref "C512") (pin "1") (pinfunction "1_1") (pintype "passive"))
      (node (ref "C513") (pin "1") (pinfunction "1_1") (pintype "passive"))
      (node (ref "C514") (pin "1") (pinfunction "1_1") (pintype "passive"))
      (node (ref "L32") (pin "2") (pinfunction "2_2") (pintype "passive"))
      (node (ref "L33") (pin "1") (pinfunction "1_1") (pintype "passive"))
      (node (ref "R368") (pin "1") (pinfunction "1_1") (pintype "passive"))
    )
    (net (code "33") (name "VCC3V3_RK628_HDMIRX") (class "Default")
      (node (ref "L34") (pin "1") (pinfunction "1_1") (pintype "passive"))
      (node (ref "R369") (pin "2") (pinfunction "2_2") (pintype "passive"))
    )
    (net (code "34") (name "VCC3V3_RK628_S0") (class "Default")
      (node (ref "C517") (pin "1") (pinfunction "1_1") (pintype "passive"))
      (node (ref "C518") (pin "1") (pinfunction "1_1") (pintype "passive"))
      (node (ref "D41") (pin "1") (pinfunction "VOUT_1") (pintype "passive"))
      (node (ref "R369") (pin "1") (pinfunction "1_1") (pintype "passive"))
      (node (ref "R370") (pin "1") (pinfunction "1_1") (pintype "passive"))
    )
    (net (code "35") (name "VCC5V0_SYS_S5") (class "Default")
      (node (ref "C477") (pin "1") (pinfunction "1_1") (pintype "passive"))
      (node (ref "C478") (pin "1") (pinfunction "1_1") (pintype "passive"))
      (node (ref "C483") (pin "1") (pinfunction "1_1") (pintype "passive"))
      (node (ref "C484") (pin "1") (pinfunction "1_1") (pintype "passive"))
      (node (ref "C489") (pin "1") (pinfunction "1_1") (pintype "passive"))
      (node (ref "C490") (pin "1") (pinfunction "1_1") (pintype "passive"))
      (node (ref "C495") (pin "1") (pinfunction "1_1") (pintype "passive"))
      (node (ref "C496") (pin "1") (pinfunction "1_1") (pintype "passive"))
      (node (ref "D35") (pin "4") (pinfunction "IN_4") (pintype "passive"))
      (node (ref "D36") (pin "4") (pinfunction "IN_4") (pintype "passive"))
      (node (ref "D37") (pin "4") (pinfunction "IN_4") (pintype "passive"))
      (node (ref "D38") (pin "4") (pinfunction "IN_4") (pintype "passive"))
      (node (ref "R364") (pin "1") (pinfunction "1_1") (pintype "passive"))
    )
    (net (code "36") (name "VCCA1V1_RK628_HDMIRX") (class "Default")
      (node (ref "C511") (pin "1") (pinfunction "1_1") (pintype "passive"))
      (node (ref "L33") (pin "2") (pinfunction "2_2") (pintype "passive"))
    )
    (net (code "37") (name "VCCA3V3_RK628_HDMIRX") (class "Default")
      (node (ref "C519") (pin "1") (pinfunction "1_1") (pintype "passive"))
      (node (ref "L34") (pin "2") (pinfunction "2_2") (pintype "passive"))
    )
    (net (code "38") (name "VCC_1V1_NLDO_S3") (class "Default")
      (node (ref "C497") (pin "1") (pinfunction "1_1") (pintype "passive"))
      (node (ref "C498") (pin "1") (pinfunction "1_1") (pintype "passive"))
      (node (ref "C499") (pin "1") (pinfunction "1_1") (pintype "passive"))
      (node (ref "C500") (pin "1") (pinfunction "1_1") (pintype "passive"))
      (node (ref "L31") (pin "2") (pinfunction "2_2") (pintype "passive"))
      (node (ref "R358") (pin "2") (pinfunction "2_2") (pintype "passive"))
    )
    (net (code "39") (name "VCC_1V8_S0") (class "Default")
      (node (ref "C502") (pin "1") (pinfunction "1_1") (pintype "passive"))
      (node (ref "R367") (pin "1") (pinfunction "1_1") (pintype "passive"))
      (node (ref "VT27") (pin "2") (pinfunction "S_2") (pintype "passive"))
    )
    (net (code "40") (name "VCC_1V8_S3") (class "Default")
      (node (ref "C501") (pin "1") (pinfunction "1_1") (pintype "passive"))
      (node (ref "VT27") (pin "3") (pinfunction "D_3") (pintype "passive"))
    )
    (net (code "41") (name "VCC_2V0_PLDO_S3") (class "Default")
      (node (ref "C491") (pin "1") (pinfunction "1_1") (pintype "passive"))
      (node (ref "C492") (pin "1") (pinfunction "1_1") (pintype "passive"))
      (node (ref "C493") (pin "1") (pinfunction "1_1") (pintype "passive"))
      (node (ref "C494") (pin "1") (pinfunction "1_1") (pintype "passive"))
      (node (ref "L30") (pin "2") (pinfunction "2_2") (pintype "passive"))
      (node (ref "R357") (pin "1") (pinfunction "1_1") (pintype "passive"))
    )
    (net (code "42") (name "VCC_3V3_S0") (class "Default")
      (node (ref "C505") (pin "1") (pinfunction "1_1") (pintype "passive"))
      (node (ref "C506") (pin "1") (pinfunction "1_1") (pintype "passive"))
      (node (ref "D39") (pin "1") (pinfunction "VOUT_1") (pintype "passive"))
    )
    (net (code "43") (name "VCC_3V3_S3") (class "Default")
      (node (ref "C503") (pin "1") (pinfunction "1_1") (pintype "passive"))
      (node (ref "C504") (pin "1") (pinfunction "1_1") (pintype "passive"))
      (node (ref "C508") (pin "1") (pinfunction "1_1") (pintype "passive"))
      (node (ref "C509") (pin "1") (pinfunction "1_1") (pintype "passive"))
      (node (ref "C515") (pin "1") (pinfunction "1_1") (pintype "passive"))
      (node (ref "C516") (pin "1") (pinfunction "1_1") (pintype "passive"))
      (node (ref "D39") (pin "5") (pinfunction "VIN_5") (pintype "passive"))
      (node (ref "D40") (pin "4") (pinfunction "IN_4") (pintype "passive"))
      (node (ref "D41") (pin "5") (pinfunction "VIN_5") (pintype "passive"))
      (node (ref "R363") (pin "1") (pinfunction "1_1") (pintype "passive"))
    )
  )
)
